# Breadboard_Power_Supply_1.net
KiCad netlist of a schematic drawn in EAGLE
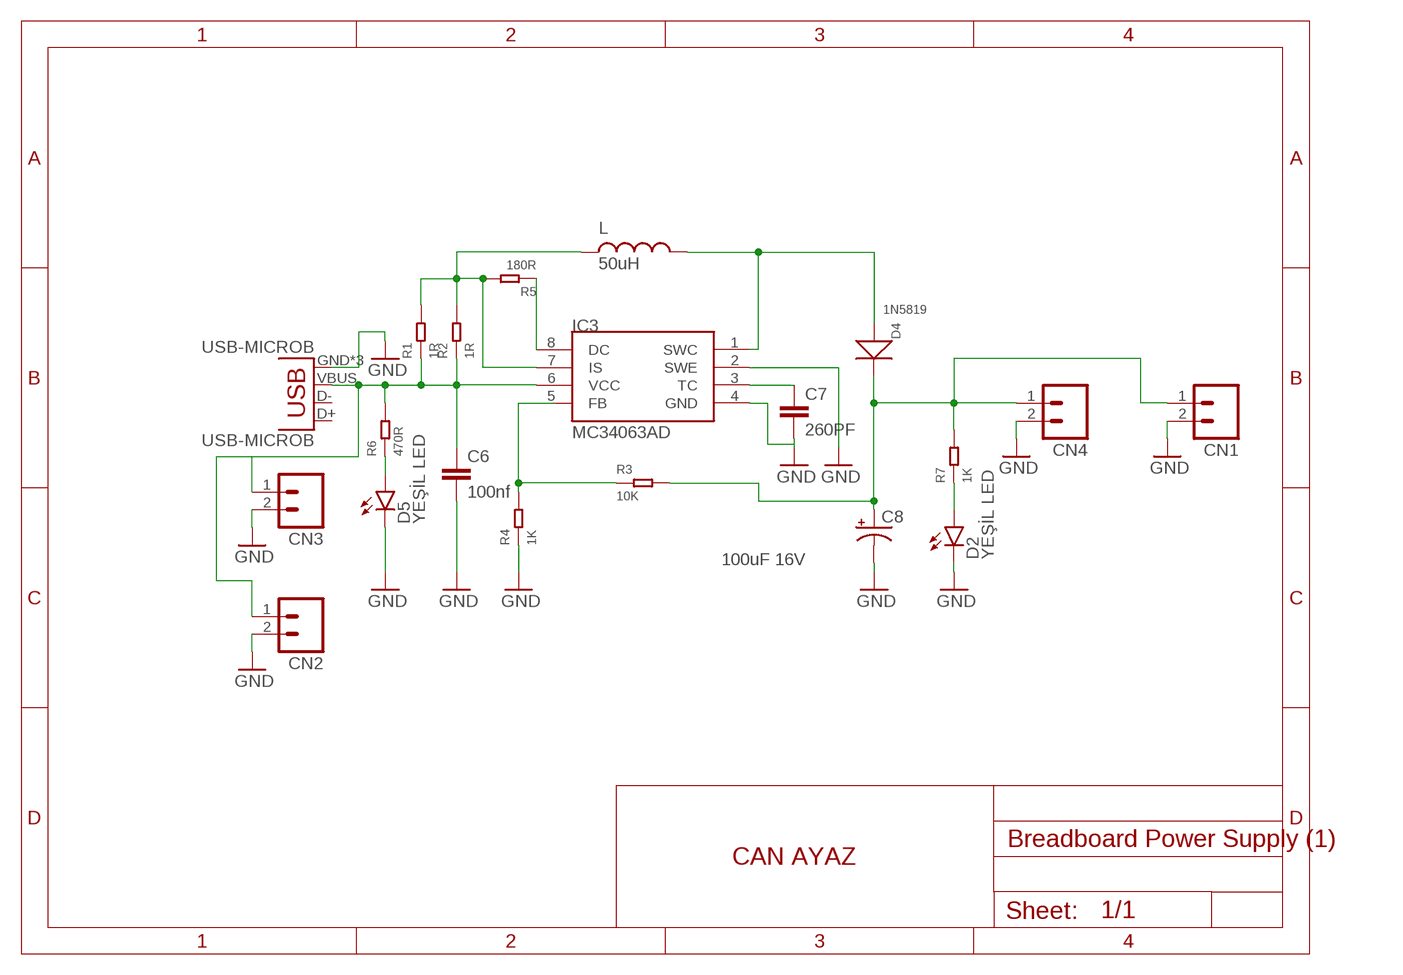
[diagram p0: schematic, sheet 1]

(export (version "E")
  (design (tool "Eeschema 10.0.6"))
  (components
    (comp (ref "C6")
      (value "100nf")
      (footprint "eagle-import:1206")
      (libsource (lib "eagle-import") (part "CAP1206"))
    )
    (comp (ref "C7")
      (value "260PF")
      (footprint "eagle-import:1206")
      (libsource (lib "eagle-import") (part "CAP1206"))
    )
    (comp (ref "C8")
      (value "100uF 16V")
      (footprint "eagle-import:PANASONIC_G")
      (libsource (lib "eagle-import") (part "CAP_POLG"))
    )
    (comp (ref "CN1")
      (value "M02")
      (footprint "eagle-import:02P")
      (libsource (lib "eagle-import") (part "M02"))
    )
    (comp (ref "CN2")
      (value "M02")
      (footprint "eagle-import:02P")
      (libsource (lib "eagle-import") (part "M02"))
    )
    (comp (ref "CN3")
      (value "M02")
      (footprint "eagle-import:02P")
      (libsource (lib "eagle-import") (part "M02"))
    )
    (comp (ref "CN4")
      (value "M02")
      (footprint "eagle-import:02P")
      (libsource (lib "eagle-import") (part "M02"))
    )
    (comp (ref "D2")
      (value "YEŞİL LED")
      (footprint "eagle-import:LED-1206")
      (libsource (lib "eagle-import") (part "LED1206"))
    )
    (comp (ref "D4")
      (value "1N5819")
      (footprint "eagle-import:DO-214AC")
      (libsource (lib "eagle-import") (part "DIODE'SMA'"))
    )
    (comp (ref "D5")
      (value "YEŞİL LED")
      (footprint "eagle-import:LED-1206")
      (libsource (lib "eagle-import") (part "LED1206"))
    )
    (comp (ref "IC3")
      (value "MC34063AD")
      (footprint "eagle-import:SOIC8")
      (libsource (lib "eagle-import") (part "MC34063AD"))
    )
    (comp (ref "L")
      (value "50uH")
      (footprint "eagle-import:MSS1260")
      (libsource (lib "eagle-import") (part "MSS1260"))
    )
    (comp (ref "R1")
      (value "1R")
      (footprint "eagle-import:R1206")
      (libsource (lib "eagle-import") (part "RES-1206"))
    )
    (comp (ref "R2")
      (value "1R")
      (footprint "eagle-import:R1206")
      (libsource (lib "eagle-import") (part "RES-1206"))
    )
    (comp (ref "R3")
      (value "10K")
      (footprint "eagle-import:R1206")
      (libsource (lib "eagle-import") (part "RES-1206"))
    )
    (comp (ref "R4")
      (value "1K")
      (footprint "eagle-import:R1206")
      (libsource (lib "eagle-import") (part "RES-1206"))
    )
    (comp (ref "R5")
      (value "180R")
      (footprint "eagle-import:R1206")
      (libsource (lib "eagle-import") (part "RES-1206"))
    )
    (comp (ref "R6")
      (value "470R")
      (footprint "eagle-import:R1206")
      (libsource (lib "eagle-import") (part "RES-1206"))
    )
    (comp (ref "R7")
      (value "1K")
      (footprint "eagle-import:R1206")
      (libsource (lib "eagle-import") (part "RES-1206"))
    )
    (comp (ref "USB-MICROB")
      (value "USB-MICROB")
      (footprint "eagle-import:USB-MICROB")
      (libsource (lib "eagle-import") (part "USB-MICROB"))
    )
  )
  (nets
    (net (code "1") (name "GND") (class "Default")
      (node (ref "C6") (pin "2") (pinfunction "2_2") (pintype "passive"))
      (node (ref "C7") (pin "2") (pinfunction "2_2") (pintype "passive"))
      (node (ref "C8") (pin "-") (pinfunction "-_-") (pintype "passive"))
      (node (ref "CN1") (pin "2") (pinfunction "2_2") (pintype "passive"))
      (node (ref "CN2") (pin "2") (pinfunction "2_2") (pintype "passive"))
      (node (ref "CN3") (pin "2") (pinfunction "2_2") (pintype "passive"))
      (node (ref "CN4") (pin "2") (pinfunction "2_2") (pintype "passive"))
      (node (ref "D2") (pin "C") (pinfunction "C_C") (pintype "passive"))
      (node (ref "D5") (pin "C") (pinfunction "C_C") (pintype "passive"))
      (node (ref "IC3") (pin "2") (pinfunction "SWE_2") (pintype "passive"))
      (node (ref "IC3") (pin "4") (pinfunction "GND_4") (pintype "passive"))
      (node (ref "R4") (pin "1") (pinfunction "1_1") (pintype "passive"))
      (node (ref "USB-MICROB") (pin "GND") (pinfunction "GND_GND") (pintype "bidirectional"))
      (node (ref "USB-MICROB") (pin "MT1") (pinfunction "GND_MT1") (pintype "bidirectional"))
      (node (ref "USB-MICROB") (pin "MT2") (pinfunction "GND_MT2") (pintype "bidirectional"))
    )
    (net (code "2") (name "Net-(D2-PadA)") (class "Default")
      (node (ref "D2") (pin "A") (pinfunction "A_A") (pintype "passive"))
      (node (ref "R7") (pin "1") (pinfunction "1_1") (pintype "passive"))
    )
    (net (code "3") (name "Net-(D4-+)") (class "Default")
      (node (ref "D4") (pin "1") (pinfunction "+_1") (pintype "passive"))
      (node (ref "IC3") (pin "1") (pinfunction "SWC_1") (pintype "passive"))
      (node (ref "L") (pin "P$1") (pinfunction "P$1_P$1") (pintype "passive"))
    )
    (net (code "4") (name "Net-(D4--)") (class "Default")
      (node (ref "C8") (pin "+") (pinfunction "+_+") (pintype "passive"))
      (node (ref "CN1") (pin "1") (pinfunction "1_1") (pintype "passive"))
      (node (ref "CN4") (pin "1") (pinfunction "1_1") (pintype "passive"))
      (node (ref "D4") (pin "2") (pinfunction "-_2") (pintype "passive"))
      (node (ref "R3") (pin "2") (pinfunction "2_2") (pintype "passive"))
      (node (ref "R7") (pin "2") (pinfunction "2_2") (pintype "passive"))
    )
    (net (code "5") (name "Net-(D5-PadA)") (class "Default")
      (node (ref "D5") (pin "A") (pinfunction "A_A") (pintype "passive"))
      (node (ref "R6") (pin "1") (pinfunction "1_1") (pintype "passive"))
    )
    (net (code "6") (name "Net-(IC3-DC)") (class "Default")
      (node (ref "IC3") (pin "8") (pinfunction "DC_8") (pintype "passive"))
      (node (ref "R5") (pin "1") (pinfunction "1_1") (pintype "passive"))
    )
    (net (code "7") (name "Net-(IC3-FB)") (class "Default")
      (node (ref "IC3") (pin "5") (pinfunction "FB_5") (pintype "passive"))
      (node (ref "R3") (pin "1") (pinfunction "1_1") (pintype "passive"))
      (node (ref "R4") (pin "2") (pinfunction "2_2") (pintype "passive"))
    )
    (net (code "8") (name "Net-(IC3-IS)") (class "Default")
      (node (ref "IC3") (pin "7") (pinfunction "IS_7") (pintype "passive"))
      (node (ref "L") (pin "P$2") (pinfunction "P$2_P$2") (pintype "passive"))
      (node (ref "R1") (pin "2") (pinfunction "2_2") (pintype "passive"))
      (node (ref "R2") (pin "2") (pinfunction "2_2") (pintype "passive"))
      (node (ref "R5") (pin "2") (pinfunction "2_2") (pintype "passive"))
    )
    (net (code "9") (name "Net-(IC3-TC)") (class "Default")
      (node (ref "C7") (pin "1") (pinfunction "1_1") (pintype "passive"))
      (node (ref "IC3") (pin "3") (pinfunction "TC_3") (pintype "passive"))
    )
    (net (code "10") (name "Net-(IC3-VCC)") (class "Default")
      (node (ref "C6") (pin "1") (pinfunction "1_1") (pintype "passive"))
      (node (ref "CN2") (pin "1") (pinfunction "1_1") (pintype "passive"))
      (node (ref "CN3") (pin "1") (pinfunction "1_1") (pintype "passive"))
      (node (ref "IC3") (pin "6") (pinfunction "VCC_6") (pintype "passive"))
      (node (ref "R1") (pin "1") (pinfunction "1_1") (pintype "passive"))
      (node (ref "R2") (pin "1") (pinfunction "1_1") (pintype "passive"))
      (node (ref "R6") (pin "2") (pinfunction "2_2") (pintype "passive"))
      (node (ref "USB-MICROB") (pin "VBUS") (pinfunction "VBUS_VBUS") (pintype "bidirectional"))
    )
    (net (code "11") (name "unconnected-(USB-MICROB-PadD+)") (class "Default")
      (node (ref "USB-MICROB") (pin "D+") (pinfunction "D+_D+") (pintype "bidirectional"))
    )
    (net (code "12") (name "unconnected-(USB-MICROB-PadD-)") (class "Default")
      (node (ref "USB-MICROB") (pin "D-") (pinfunction "D-_D-") (pintype "bidirectional"))
    )
  )
)
